# RedditSecretSanta2020_2.net
KiCad netlist of a schematic drawn in EAGLE
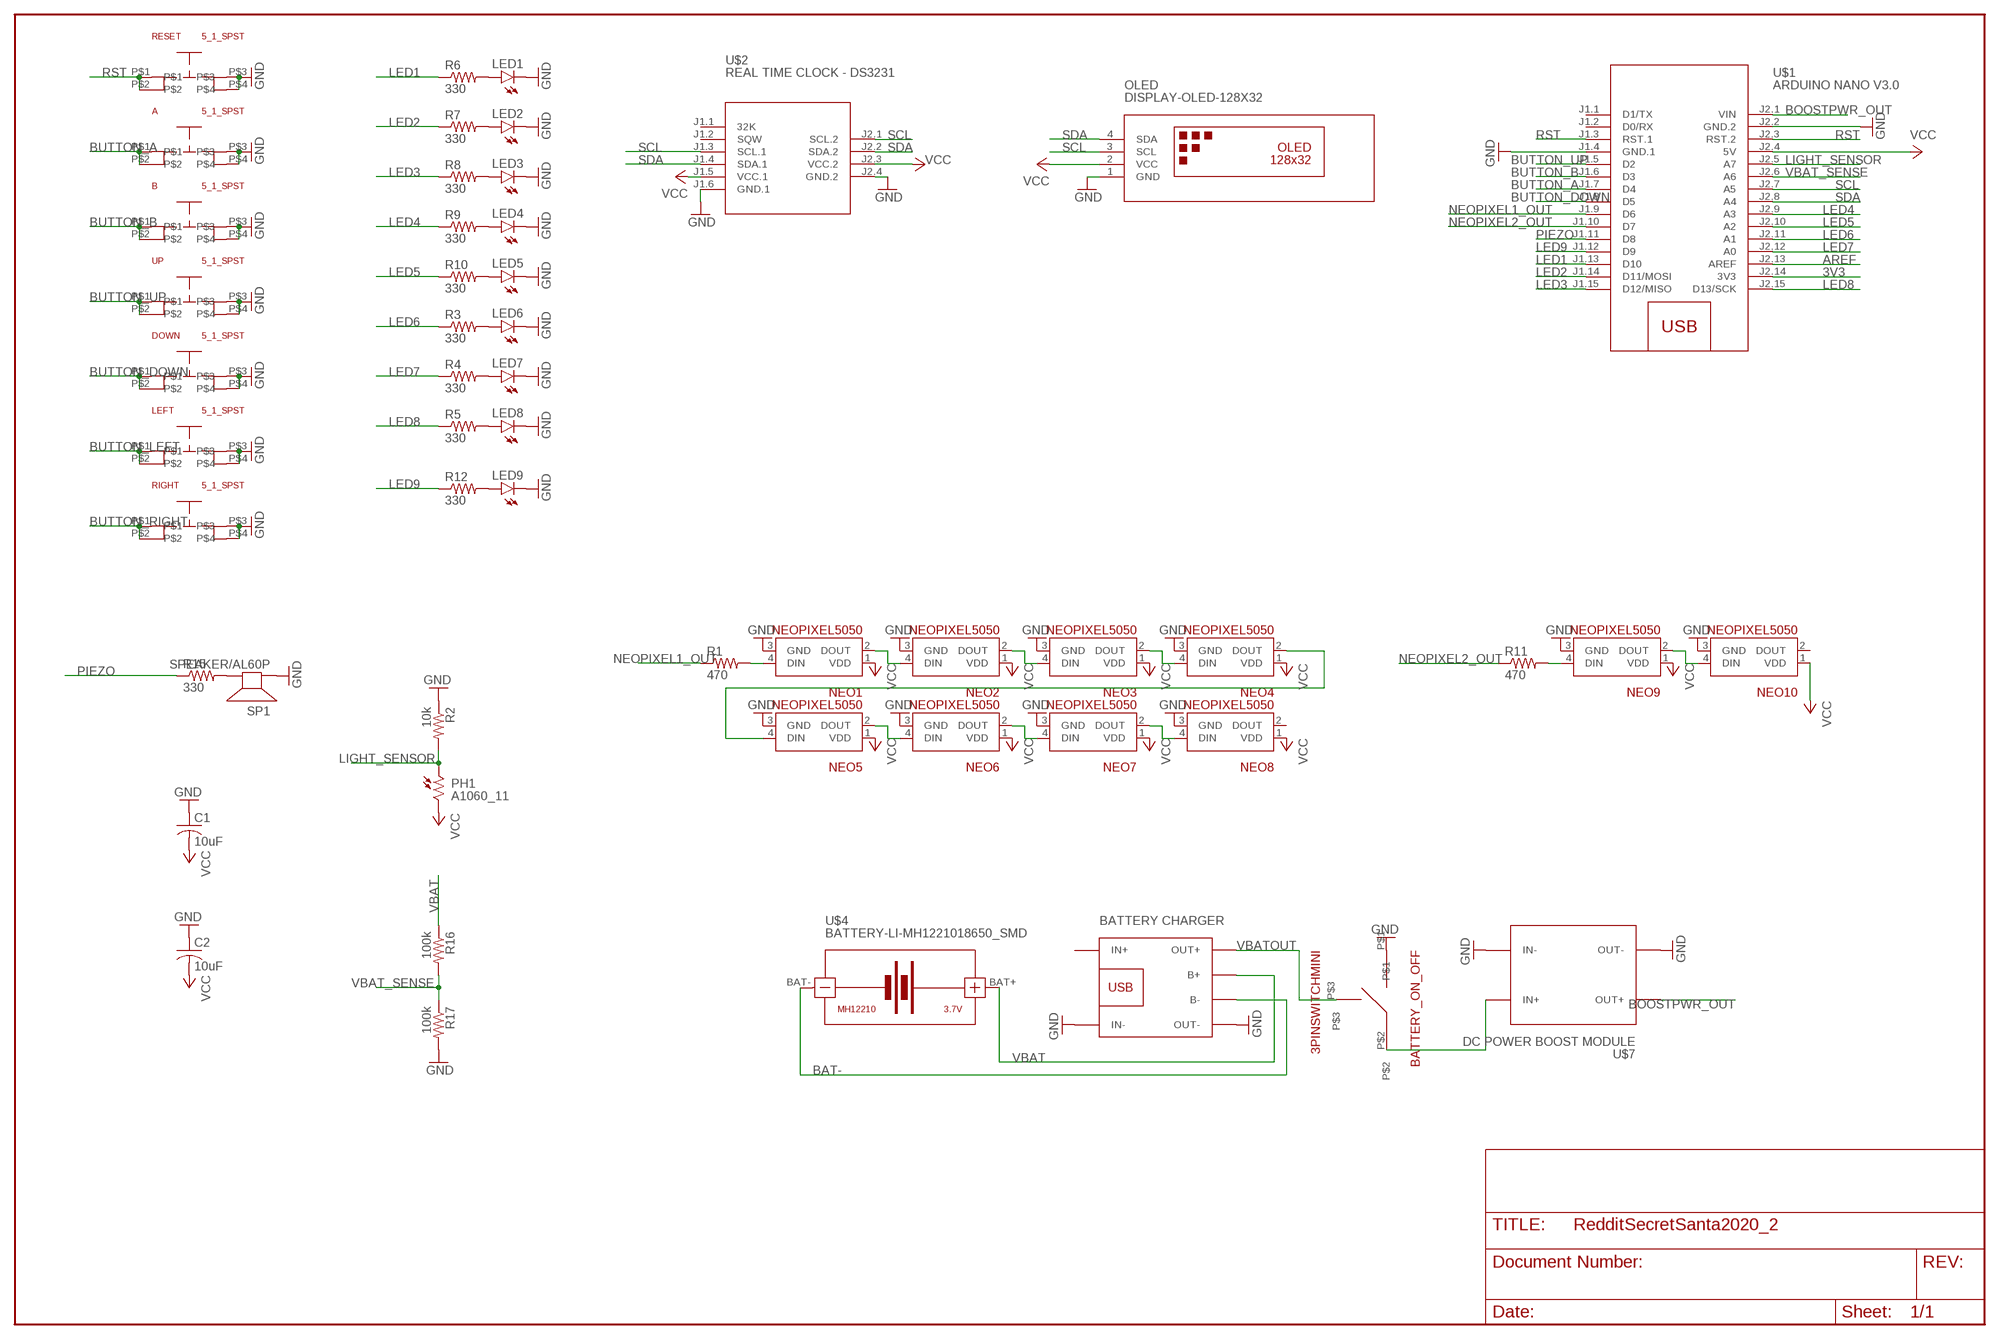
[diagram p0: schematic, sheet 1]

(export (version "E")
  (design (tool "Eeschema 10.0.6"))
  (components
    (comp (ref "A")
      (value "5_1_SPST")
      (footprint "eagle-import:5_1_SPST")
      (libsource (lib "eagle-import") (part "5_1_SPST"))
    )
    (comp (ref "B")
      (value "5_1_SPST")
      (footprint "eagle-import:5_1_SPST")
      (libsource (lib "eagle-import") (part "5_1_SPST"))
    )
    (comp (ref "BATTERY_ON_OFF")
      (value "3PINSWITCHMINI")
      (footprint "eagle-import:3PINMINI")
      (libsource (lib "eagle-import") (part "3PINSWITCHMINI"))
    )
    (comp (ref "C1")
      (value "10uF")
      (footprint "eagle-import:C0805")
      (libsource (lib "eagle-import") (part "C-USC0805"))
    )
    (comp (ref "C2")
      (value "10uF")
      (footprint "eagle-import:C0805")
      (libsource (lib "eagle-import") (part "C-USC0805"))
    )
    (comp (ref "DOWN")
      (value "5_1_SPST")
      (footprint "eagle-import:5_1_SPST")
      (libsource (lib "eagle-import") (part "5_1_SPST"))
    )
    (comp (ref "LED1")
      (value "LEDSML0805")
      (footprint "eagle-import:SML0805")
      (libsource (lib "eagle-import") (part "LEDSML0805"))
    )
    (comp (ref "LED2")
      (value "LEDSML0805")
      (footprint "eagle-import:SML0805")
      (libsource (lib "eagle-import") (part "LEDSML0805"))
    )
    (comp (ref "LED3")
      (value "LEDSML0805")
      (footprint "eagle-import:SML0805")
      (libsource (lib "eagle-import") (part "LEDSML0805"))
    )
    (comp (ref "LED4")
      (value "LEDSML0805")
      (footprint "eagle-import:SML0805")
      (libsource (lib "eagle-import") (part "LEDSML0805"))
    )
    (comp (ref "LED5")
      (value "LEDSML0805")
      (footprint "eagle-import:SML0805")
      (libsource (lib "eagle-import") (part "LEDSML0805"))
    )
    (comp (ref "LED6")
      (value "LEDSML0805")
      (footprint "eagle-import:SML0805")
      (libsource (lib "eagle-import") (part "LEDSML0805"))
    )
    (comp (ref "LED7")
      (value "LEDSML0805")
      (footprint "eagle-import:SML0805")
      (libsource (lib "eagle-import") (part "LEDSML0805"))
    )
    (comp (ref "LED8")
      (value "LEDSML0805")
      (footprint "eagle-import:SML0805")
      (libsource (lib "eagle-import") (part "LEDSML0805"))
    )
    (comp (ref "LED9")
      (value "LEDSML0805")
      (footprint "eagle-import:SML0805")
      (libsource (lib "eagle-import") (part "LEDSML0805"))
    )
    (comp (ref "LEFT")
      (value "5_1_SPST")
      (footprint "eagle-import:5_1_SPST")
      (libsource (lib "eagle-import") (part "5_1_SPST"))
    )
    (comp (ref "NEO1")
      (value "NEOPIXEL5050")
      (footprint "eagle-import:NEOPIXEL5050")
      (libsource (lib "eagle-import") (part "NEOPIXEL5050"))
    )
    (comp (ref "NEO2")
      (value "NEOPIXEL5050")
      (footprint "eagle-import:NEOPIXEL5050")
      (libsource (lib "eagle-import") (part "NEOPIXEL5050"))
    )
    (comp (ref "NEO3")
      (value "NEOPIXEL5050")
      (footprint "eagle-import:NEOPIXEL5050")
      (libsource (lib "eagle-import") (part "NEOPIXEL5050"))
    )
    (comp (ref "NEO4")
      (value "NEOPIXEL5050")
      (footprint "eagle-import:NEOPIXEL5050")
      (libsource (lib "eagle-import") (part "NEOPIXEL5050"))
    )
    (comp (ref "NEO5")
      (value "NEOPIXEL5050")
      (footprint "eagle-import:NEOPIXEL5050")
      (libsource (lib "eagle-import") (part "NEOPIXEL5050"))
    )
    (comp (ref "NEO6")
      (value "NEOPIXEL5050")
      (footprint "eagle-import:NEOPIXEL5050")
      (libsource (lib "eagle-import") (part "NEOPIXEL5050"))
    )
    (comp (ref "NEO7")
      (value "NEOPIXEL5050")
      (footprint "eagle-import:NEOPIXEL5050")
      (libsource (lib "eagle-import") (part "NEOPIXEL5050"))
    )
    (comp (ref "NEO8")
      (value "NEOPIXEL5050")
      (footprint "eagle-import:NEOPIXEL5050")
      (libsource (lib "eagle-import") (part "NEOPIXEL5050"))
    )
    (comp (ref "NEO9")
      (value "NEOPIXEL5050")
      (footprint "eagle-import:NEOPIXEL5050")
      (libsource (lib "eagle-import") (part "NEOPIXEL5050"))
    )
    (comp (ref "NEO10")
      (value "NEOPIXEL5050")
      (footprint "eagle-import:NEOPIXEL5050")
      (libsource (lib "eagle-import") (part "NEOPIXEL5050"))
    )
    (comp (ref "OLED")
      (value "DISPLAY-OLED-128X32")
      (footprint "eagle-import:DISPLAY-OLED-128X32")
      (libsource (lib "eagle-import") (part "DISPLAY-OLED-128X32"))
    )
    (comp (ref "PH1")
      (value "A1060_11")
      (footprint "eagle-import:T0-46-A10XX")
      (libsource (lib "eagle-import") (part "A1060_11"))
    )
    (comp (ref "R1")
      (value "470")
      (footprint "eagle-import:R0805")
      (libsource (lib "eagle-import") (part "R-US_R0805"))
    )
    (comp (ref "R2")
      (value "10k")
      (footprint "eagle-import:R0805")
      (libsource (lib "eagle-import") (part "R-US_R0805"))
    )
    (comp (ref "R3")
      (value "330")
      (footprint "eagle-import:R0805")
      (libsource (lib "eagle-import") (part "R-US_R0805"))
    )
    (comp (ref "R4")
      (value "330")
      (footprint "eagle-import:R0805")
      (libsource (lib "eagle-import") (part "R-US_R0805"))
    )
    (comp (ref "R5")
      (value "330")
      (footprint "eagle-import:R0805")
      (libsource (lib "eagle-import") (part "R-US_R0805"))
    )
    (comp (ref "R6")
      (value "330")
      (footprint "eagle-import:R0805")
      (libsource (lib "eagle-import") (part "R-US_R0805"))
    )
    (comp (ref "R7")
      (value "330")
      (footprint "eagle-import:R0805")
      (libsource (lib "eagle-import") (part "R-US_R0805"))
    )
    (comp (ref "R8")
      (value "330")
      (footprint "eagle-import:R0805")
      (libsource (lib "eagle-import") (part "R-US_R0805"))
    )
    (comp (ref "R9")
      (value "330")
      (footprint "eagle-import:R0805")
      (libsource (lib "eagle-import") (part "R-US_R0805"))
    )
    (comp (ref "R10")
      (value "330")
      (footprint "eagle-import:R0805")
      (libsource (lib "eagle-import") (part "R-US_R0805"))
    )
    (comp (ref "R11")
      (value "470")
      (footprint "eagle-import:R0805")
      (libsource (lib "eagle-import") (part "R-US_R0805"))
    )
    (comp (ref "R12")
      (value "330")
      (footprint "eagle-import:R0805")
      (libsource (lib "eagle-import") (part "R-US_R0805"))
    )
    (comp (ref "R15")
      (value "330")
      (footprint "eagle-import:R0805")
      (libsource (lib "eagle-import") (part "R-US_R0805"))
    )
    (comp (ref "R16")
      (value "100k")
      (footprint "eagle-import:R0805")
      (libsource (lib "eagle-import") (part "R-US_R0805"))
    )
    (comp (ref "R17")
      (value "100k")
      (footprint "eagle-import:R0805")
      (libsource (lib "eagle-import") (part "R-US_R0805"))
    )
    (comp (ref "RESET")
      (value "5_1_SPST")
      (footprint "eagle-import:5_1_SPST")
      (libsource (lib "eagle-import") (part "5_1_SPST"))
    )
    (comp (ref "RIGHT")
      (value "5_1_SPST")
      (footprint "eagle-import:5_1_SPST")
      (libsource (lib "eagle-import") (part "5_1_SPST"))
    )
    (comp (ref "SP1")
      (value "SPEAKER/AL60P")
      (footprint "eagle-import:AL60P")
      (libsource (lib "eagle-import") (part "SPEAKER/AL60P"))
    )
    (comp (ref "U$1")
      (value "ARDUINO NANO V3.0")
      (footprint "eagle-import:ARDUINO-NANO-3.0")
      (libsource (lib "eagle-import") (part "ARDUINO-NANO-3.0"))
    )
    (comp (ref "U$2")
      (value "REAL TIME CLOCK - DS3231")
      (footprint "eagle-import:RTC-DS3231-AT24C32")
      (libsource (lib "eagle-import") (part "RTC-DS3231-AT24C32"))
    )
    (comp (ref "U$4")
      (value "BATTERY-LI-MH1221018650_SMD")
      (footprint "eagle-import:BATTERY_18650_SMD")
      (libsource (lib "eagle-import") (part "BATTERY-LI-MH1221018650_SMD"))
    )
    (comp (ref "U$6")
      (value "BATTERY CHARGER")
      (footprint "eagle-import:BAT_CHARGE_LOW_FP")
      (libsource (lib "eagle-import") (part "BATTERY-CHARGER-LI-PROTLOW_FP"))
    )
    (comp (ref "U$7")
      (value "DC POWER BOOST MODULE")
      (footprint "eagle-import:DC-DC-STEP-UP-LOW_FP")
      (libsource (lib "eagle-import") (part "DC-DC-STEP-UP-MT3608LOW_FP"))
    )
    (comp (ref "UP")
      (value "5_1_SPST")
      (footprint "eagle-import:5_1_SPST")
      (libsource (lib "eagle-import") (part "5_1_SPST"))
    )
  )
  (nets
    (net (code "1") (name "/3V3") (class "Default")
      (node (ref "U$1") (pin "J2.14") (pinfunction "3V3_J2.14") (pintype "power_in"))
    )
    (net (code "2") (name "/AREF") (class "Default")
      (node (ref "U$1") (pin "J2.13") (pinfunction "AREF_J2.13") (pintype "bidirectional"))
    )
    (net (code "3") (name "/BAT-") (class "Default")
      (node (ref "U$4") (pin "BAT-") (pinfunction "BAT-_BAT-") (pintype "power_in"))
      (node (ref "U$6") (pin "B-") (pinfunction "B-_B-") (pintype "bidirectional"))
    )
    (net (code "4") (name "/BOOSTPWR_OUT") (class "Default")
      (node (ref "U$1") (pin "J2.1") (pinfunction "VIN_J2.1") (pintype "power_in"))
      (node (ref "U$7") (pin "OUT+") (pinfunction "OUT+_OUT+") (pintype "bidirectional"))
    )
    (net (code "5") (name "/BUTTON_A") (class "Default")
      (node (ref "A") (pin "P$1") (pinfunction "P$1_P$1") (pintype "bidirectional"))
      (node (ref "A") (pin "P$2") (pinfunction "P$2_P$2") (pintype "bidirectional"))
      (node (ref "U$1") (pin "J1.7") (pinfunction "D4_J1.7") (pintype "bidirectional"))
    )
    (net (code "6") (name "/BUTTON_B") (class "Default")
      (node (ref "B") (pin "P$1") (pinfunction "P$1_P$1") (pintype "bidirectional"))
      (node (ref "B") (pin "P$2") (pinfunction "P$2_P$2") (pintype "bidirectional"))
      (node (ref "U$1") (pin "J1.6") (pinfunction "D3_J1.6") (pintype "bidirectional"))
    )
    (net (code "7") (name "/BUTTON_DOWN") (class "Default")
      (node (ref "DOWN") (pin "P$1") (pinfunction "P$1_P$1") (pintype "bidirectional"))
      (node (ref "DOWN") (pin "P$2") (pinfunction "P$2_P$2") (pintype "bidirectional"))
      (node (ref "U$1") (pin "J1.8") (pinfunction "D5_J1.8") (pintype "bidirectional"))
    )
    (net (code "8") (name "/BUTTON_LEFT") (class "Default")
      (node (ref "LEFT") (pin "P$1") (pinfunction "P$1_P$1") (pintype "bidirectional"))
      (node (ref "LEFT") (pin "P$2") (pinfunction "P$2_P$2") (pintype "bidirectional"))
    )
    (net (code "9") (name "/BUTTON_RIGHT") (class "Default")
      (node (ref "RIGHT") (pin "P$1") (pinfunction "P$1_P$1") (pintype "bidirectional"))
      (node (ref "RIGHT") (pin "P$2") (pinfunction "P$2_P$2") (pintype "bidirectional"))
    )
    (net (code "10") (name "/BUTTON_UP") (class "Default")
      (node (ref "U$1") (pin "J1.5") (pinfunction "D2_J1.5") (pintype "bidirectional"))
      (node (ref "UP") (pin "P$1") (pinfunction "P$1_P$1") (pintype "bidirectional"))
      (node (ref "UP") (pin "P$2") (pinfunction "P$2_P$2") (pintype "bidirectional"))
    )
    (net (code "11") (name "/LED1") (class "Default")
      (node (ref "R6") (pin "1") (pinfunction "1_1") (pintype "passive"))
      (node (ref "U$1") (pin "J1.13") (pinfunction "D10_J1.13") (pintype "bidirectional"))
    )
    (net (code "12") (name "/LED2") (class "Default")
      (node (ref "R7") (pin "1") (pinfunction "1_1") (pintype "passive"))
      (node (ref "U$1") (pin "J1.14") (pinfunction "D11/MOSI_J1.14") (pintype "bidirectional"))
    )
    (net (code "13") (name "/LED3") (class "Default")
      (node (ref "R8") (pin "1") (pinfunction "1_1") (pintype "passive"))
      (node (ref "U$1") (pin "J1.15") (pinfunction "D12/MISO_J1.15") (pintype "bidirectional"))
    )
    (net (code "14") (name "/LED4") (class "Default")
      (node (ref "R9") (pin "1") (pinfunction "1_1") (pintype "passive"))
      (node (ref "U$1") (pin "J2.9") (pinfunction "A3_J2.9") (pintype "bidirectional"))
    )
    (net (code "15") (name "/LED5") (class "Default")
      (node (ref "R10") (pin "1") (pinfunction "1_1") (pintype "passive"))
      (node (ref "U$1") (pin "J2.10") (pinfunction "A2_J2.10") (pintype "bidirectional"))
    )
    (net (code "16") (name "/LED6") (class "Default")
      (node (ref "R3") (pin "1") (pinfunction "1_1") (pintype "passive"))
      (node (ref "U$1") (pin "J2.11") (pinfunction "A1_J2.11") (pintype "bidirectional"))
    )
    (net (code "17") (name "/LED7") (class "Default")
      (node (ref "R4") (pin "1") (pinfunction "1_1") (pintype "passive"))
      (node (ref "U$1") (pin "J2.12") (pinfunction "A0_J2.12") (pintype "bidirectional"))
    )
    (net (code "18") (name "/LED8") (class "Default")
      (node (ref "R5") (pin "1") (pinfunction "1_1") (pintype "passive"))
      (node (ref "U$1") (pin "J2.15") (pinfunction "D13/SCK_J2.15") (pintype "bidirectional"))
    )
    (net (code "19") (name "/LED9") (class "Default")
      (node (ref "R12") (pin "1") (pinfunction "1_1") (pintype "passive"))
      (node (ref "U$1") (pin "J1.12") (pinfunction "D9_J1.12") (pintype "bidirectional"))
    )
    (net (code "20") (name "/LIGHT_SENSOR") (class "Default")
      (node (ref "PH1") (pin "1") (pinfunction "1_1") (pintype "passive"))
      (node (ref "R2") (pin "2") (pinfunction "2_2") (pintype "passive"))
      (node (ref "U$1") (pin "J2.5") (pinfunction "A7_J2.5") (pintype "bidirectional"))
    )
    (net (code "21") (name "/NEOPIXEL1_OUT") (class "Default")
      (node (ref "R1") (pin "1") (pinfunction "1_1") (pintype "passive"))
      (node (ref "U$1") (pin "J1.9") (pinfunction "D6_J1.9") (pintype "bidirectional"))
    )
    (net (code "22") (name "/NEOPIXEL2_OUT") (class "Default")
      (node (ref "R11") (pin "1") (pinfunction "1_1") (pintype "passive"))
      (node (ref "U$1") (pin "J1.10") (pinfunction "D7_J1.10") (pintype "bidirectional"))
    )
    (net (code "23") (name "/PIEZO") (class "Default")
      (node (ref "R15") (pin "1") (pinfunction "1_1") (pintype "passive"))
      (node (ref "U$1") (pin "J1.11") (pinfunction "D8_J1.11") (pintype "bidirectional"))
    )
    (net (code "24") (name "/RST") (class "Default")
      (node (ref "RESET") (pin "P$1") (pinfunction "P$1_P$1") (pintype "bidirectional"))
      (node (ref "RESET") (pin "P$2") (pinfunction "P$2_P$2") (pintype "bidirectional"))
      (node (ref "U$1") (pin "J1.3") (pinfunction "RST.1_J1.3") (pintype "bidirectional"))
      (node (ref "U$1") (pin "J2.3") (pinfunction "RST.2_J2.3") (pintype "bidirectional"))
    )
    (net (code "25") (name "/SCL") (class "Default")
      (node (ref "OLED") (pin "3") (pinfunction "SCL_3") (pintype "bidirectional"))
      (node (ref "U$1") (pin "J2.7") (pinfunction "A5_J2.7") (pintype "bidirectional"))
      (node (ref "U$2") (pin "J1.3") (pinfunction "SCL.1_J1.3") (pintype "bidirectional"))
      (node (ref "U$2") (pin "J2.1") (pinfunction "SCL.2_J2.1") (pintype "bidirectional"))
    )
    (net (code "26") (name "/SDA") (class "Default")
      (node (ref "OLED") (pin "4") (pinfunction "SDA_4") (pintype "bidirectional"))
      (node (ref "U$1") (pin "J2.8") (pinfunction "A4_J2.8") (pintype "bidirectional"))
      (node (ref "U$2") (pin "J1.4") (pinfunction "SDA.1_J1.4") (pintype "bidirectional"))
      (node (ref "U$2") (pin "J2.2") (pinfunction "SDA.2_J2.2") (pintype "bidirectional"))
    )
    (net (code "27") (name "/VBAT") (class "Default")
      (node (ref "R16") (pin "1") (pinfunction "1_1") (pintype "passive"))
      (node (ref "U$4") (pin "BAT+") (pinfunction "BAT+_BAT+") (pintype "power_in"))
      (node (ref "U$6") (pin "B+") (pinfunction "B+_B+") (pintype "bidirectional"))
    )
    (net (code "28") (name "/VBATOUT") (class "Default")
      (node (ref "BATTERY_ON_OFF") (pin "P$3") (pinfunction "P$3_P$3") (pintype "bidirectional"))
      (node (ref "U$6") (pin "OUT+") (pinfunction "OUT+_OUT+") (pintype "bidirectional"))
    )
    (net (code "29") (name "/VBAT_SENSE") (class "Default")
      (node (ref "R16") (pin "2") (pinfunction "2_2") (pintype "passive"))
      (node (ref "R17") (pin "1") (pinfunction "1_1") (pintype "passive"))
      (node (ref "U$1") (pin "J2.6") (pinfunction "A6_J2.6") (pintype "bidirectional"))
    )
    (net (code "30") (name "GND") (class "Default")
      (node (ref "A") (pin "P$3") (pinfunction "P$3_P$3") (pintype "bidirectional"))
      (node (ref "A") (pin "P$4") (pinfunction "P$4_P$4") (pintype "bidirectional"))
      (node (ref "B") (pin "P$3") (pinfunction "P$3_P$3") (pintype "bidirectional"))
      (node (ref "B") (pin "P$4") (pinfunction "P$4_P$4") (pintype "bidirectional"))
      (node (ref "BATTERY_ON_OFF") (pin "P$1") (pinfunction "P$1_P$1") (pintype "bidirectional"))
      (node (ref "C1") (pin "1") (pinfunction "1_1") (pintype "passive"))
      (node (ref "C2") (pin "1") (pinfunction "1_1") (pintype "passive"))
      (node (ref "DOWN") (pin "P$3") (pinfunction "P$3_P$3") (pintype "bidirectional"))
      (node (ref "DOWN") (pin "P$4") (pinfunction "P$4_P$4") (pintype "bidirectional"))
      (node (ref "LED1") (pin "C") (pinfunction "C_C") (pintype "passive"))
      (node (ref "LED2") (pin "C") (pinfunction "C_C") (pintype "passive"))
      (node (ref "LED3") (pin "C") (pinfunction "C_C") (pintype "passive"))
      (node (ref "LED4") (pin "C") (pinfunction "C_C") (pintype "passive"))
      (node (ref "LED5") (pin "C") (pinfunction "C_C") (pintype "passive"))
      (node (ref "LED6") (pin "C") (pinfunction "C_C") (pintype "passive"))
      (node (ref "LED7") (pin "C") (pinfunction "C_C") (pintype "passive"))
      (node (ref "LED8") (pin "C") (pinfunction "C_C") (pintype "passive"))
      (node (ref "LED9") (pin "C") (pinfunction "C_C") (pintype "passive"))
      (node (ref "LEFT") (pin "P$3") (pinfunction "P$3_P$3") (pintype "bidirectional"))
      (node (ref "LEFT") (pin "P$4") (pinfunction "P$4_P$4") (pintype "bidirectional"))
      (node (ref "NEO1") (pin "3") (pinfunction "GND_3") (pintype "bidirectional"))
      (node (ref "NEO10") (pin "3") (pinfunction "GND_3") (pintype "bidirectional"))
      (node (ref "NEO2") (pin "3") (pinfunction "GND_3") (pintype "bidirectional"))
      (node (ref "NEO3") (pin "3") (pinfunction "GND_3") (pintype "bidirectional"))
      (node (ref "NEO4") (pin "3") (pinfunction "GND_3") (pintype "bidirectional"))
      (node (ref "NEO5") (pin "3") (pinfunction "GND_3") (pintype "bidirectional"))
      (node (ref "NEO6") (pin "3") (pinfunction "GND_3") (pintype "bidirectional"))
      (node (ref "NEO7") (pin "3") (pinfunction "GND_3") (pintype "bidirectional"))
      (node (ref "NEO8") (pin "3") (pinfunction "GND_3") (pintype "bidirectional"))
      (node (ref "NEO9") (pin "3") (pinfunction "GND_3") (pintype "bidirectional"))
      (node (ref "OLED") (pin "1") (pinfunction "GND_1") (pintype "power_in"))
      (node (ref "R17") (pin "2") (pinfunction "2_2") (pintype "passive"))
      (node (ref "R2") (pin "1") (pinfunction "1_1") (pintype "passive"))
      (node (ref "RESET") (pin "P$3") (pinfunction "P$3_P$3") (pintype "bidirectional"))
      (node (ref "RESET") (pin "P$4") (pinfunction "P$4_P$4") (pintype "bidirectional"))
      (node (ref "RIGHT") (pin "P$3") (pinfunction "P$3_P$3") (pintype "bidirectional"))
      (node (ref "RIGHT") (pin "P$4") (pinfunction "P$4_P$4") (pintype "bidirectional"))
      (node (ref "SP1") (pin "1") (pinfunction "+_1") (pintype "passive"))
      (node (ref "U$1") (pin "J1.4") (pinfunction "GND.1_J1.4") (pintype "power_in"))
      (node (ref "U$1") (pin "J2.2") (pinfunction "GND.2_J2.2") (pintype "power_in"))
      (node (ref "U$2") (pin "J1.6") (pinfunction "GND.1_J1.6") (pintype "power_in"))
      (node (ref "U$2") (pin "J2.4") (pinfunction "GND.2_J2.4") (pintype "power_in"))
      (node (ref "U$6") (pin "IN-") (pinfunction "IN-_IN-") (pintype "bidirectional"))
      (node (ref "U$6") (pin "OUT-") (pinfunction "OUT-_OUT-") (pintype "bidirectional"))
      (node (ref "U$7") (pin "IN-") (pinfunction "IN-_IN-") (pintype "bidirectional"))
      (node (ref "U$7") (pin "OUT-") (pinfunction "OUT-_OUT-") (pintype "bidirectional"))
      (node (ref "UP") (pin "P$3") (pinfunction "P$3_P$3") (pintype "bidirectional"))
      (node (ref "UP") (pin "P$4") (pinfunction "P$4_P$4") (pintype "bidirectional"))
    )
    (net (code "31") (name "Net-(BATTERY_ON_OFF-PadP$2)") (class "Default")
      (node (ref "BATTERY_ON_OFF") (pin "P$2") (pinfunction "P$2_P$2") (pintype "bidirectional"))
      (node (ref "U$7") (pin "IN+") (pinfunction "IN+_IN+") (pintype "bidirectional"))
    )
    (net (code "32") (name "Net-(LED1-PadA)") (class "Default")
      (node (ref "LED1") (pin "A") (pinfunction "A_A") (pintype "passive"))
      (node (ref "R6") (pin "2") (pinfunction "2_2") (pintype "passive"))
    )
    (net (code "33") (name "Net-(LED2-PadA)") (class "Default")
      (node (ref "LED2") (pin "A") (pinfunction "A_A") (pintype "passive"))
      (node (ref "R7") (pin "2") (pinfunction "2_2") (pintype "passive"))
    )
    (net (code "34") (name "Net-(LED3-PadA)") (class "Default")
      (node (ref "LED3") (pin "A") (pinfunction "A_A") (pintype "passive"))
      (node (ref "R8") (pin "2") (pinfunction "2_2") (pintype "passive"))
    )
    (net (code "35") (name "Net-(LED4-PadA)") (class "Default")
      (node (ref "LED4") (pin "A") (pinfunction "A_A") (pintype "passive"))
      (node (ref "R9") (pin "2") (pinfunction "2_2") (pintype "passive"))
    )
    (net (code "36") (name "Net-(LED5-PadA)") (class "Default")
      (node (ref "LED5") (pin "A") (pinfunction "A_A") (pintype "passive"))
      (node (ref "R10") (pin "2") (pinfunction "2_2") (pintype "passive"))
    )
    (net (code "37") (name "Net-(LED6-PadA)") (class "Default")
      (node (ref "LED6") (pin "A") (pinfunction "A_A") (pintype "passive"))
      (node (ref "R3") (pin "2") (pinfunction "2_2") (pintype "passive"))
    )
    (net (code "38") (name "Net-(LED7-PadA)") (class "Default")
      (node (ref "LED7") (pin "A") (pinfunction "A_A") (pintype "passive"))
      (node (ref "R4") (pin "2") (pinfunction "2_2") (pintype "passive"))
    )
    (net (code "39") (name "Net-(LED8-PadA)") (class "Default")
      (node (ref "LED8") (pin "A") (pinfunction "A_A") (pintype "passive"))
      (node (ref "R5") (pin "2") (pinfunction "2_2") (pintype "passive"))
    )
    (net (code "40") (name "Net-(LED9-PadA)") (class "Default")
      (node (ref "LED9") (pin "A") (pinfunction "A_A") (pintype "passive"))
      (node (ref "R12") (pin "2") (pinfunction "2_2") (pintype "passive"))
    )
    (net (code "41") (name "Net-(NEO1-DIN)") (class "Default")
      (node (ref "NEO1") (pin "4") (pinfunction "DIN_4") (pintype "bidirectional"))
      (node (ref "R1") (pin "2") (pinfunction "2_2") (pintype "passive"))
    )
    (net (code "42") (name "Net-(NEO1-DOUT)") (class "Default")
      (node (ref "NEO1") (pin "2") (pinfunction "DOUT_2") (pintype "bidirectional"))
      (node (ref "NEO2") (pin "4") (pinfunction "DIN_4") (pintype "bidirectional"))
    )
    (net (code "43") (name "Net-(NEO2-DOUT)") (class "Default")
      (node (ref "NEO2") (pin "2") (pinfunction "DOUT_2") (pintype "bidirectional"))
      (node (ref "NEO3") (pin "4") (pinfunction "DIN_4") (pintype "bidirectional"))
    )
    (net (code "44") (name "Net-(NEO3-DOUT)") (class "Default")
      (node (ref "NEO3") (pin "2") (pinfunction "DOUT_2") (pintype "bidirectional"))
      (node (ref "NEO4") (pin "4") (pinfunction "DIN_4") (pintype "bidirectional"))
    )
    (net (code "45") (name "Net-(NEO4-DOUT)") (class "Default")
      (node (ref "NEO4") (pin "2") (pinfunction "DOUT_2") (pintype "bidirectional"))
      (node (ref "NEO5") (pin "4") (pinfunction "DIN_4") (pintype "bidirectional"))
    )
    (net (code "46") (name "Net-(NEO5-DOUT)") (class "Default")
      (node (ref "NEO5") (pin "2") (pinfunction "DOUT_2") (pintype "bidirectional"))
      (node (ref "NEO6") (pin "4") (pinfunction "DIN_4") (pintype "bidirectional"))
    )
    (net (code "47") (name "Net-(NEO6-DOUT)") (class "Default")
      (node (ref "NEO6") (pin "2") (pinfunction "DOUT_2") (pintype "bidirectional"))
      (node (ref "NEO7") (pin "4") (pinfunction "DIN_4") (pintype "bidirectional"))
    )
    (net (code "48") (name "Net-(NEO7-DOUT)") (class "Default")
      (node (ref "NEO7") (pin "2") (pinfunction "DOUT_2") (pintype "bidirectional"))
      (node (ref "NEO8") (pin "4") (pinfunction "DIN_4") (pintype "bidirectional"))
    )
    (net (code "49") (name "Net-(NEO9-DIN)") (class "Default")
      (node (ref "NEO9") (pin "4") (pinfunction "DIN_4") (pintype "bidirectional"))
      (node (ref "R11") (pin "2") (pinfunction "2_2") (pintype "passive"))
    )
    (net (code "50") (name "Net-(NEO10-DIN)") (class "Default")
      (node (ref "NEO10") (pin "4") (pinfunction "DIN_4") (pintype "bidirectional"))
      (node (ref "NEO9") (pin "2") (pinfunction "DOUT_2") (pintype "bidirectional"))
    )
    (net (code "51") (name "Net-(SP1--)") (class "Default")
      (node (ref "R15") (pin "2") (pinfunction "2_2") (pintype "passive"))
      (node (ref "SP1") (pin "2") (pinfunction "-_2") (pintype "passive"))
    )
    (net (code "52") (name "VCC") (class "Default")
      (node (ref "C1") (pin "2") (pinfunction "2_2") (pintype "passive"))
      (node (ref "C2") (pin "2") (pinfunction "2_2") (pintype "passive"))
      (node (ref "NEO1") (pin "1") (pinfunction "VDD_1") (pintype "bidirectional"))
      (node (ref "NEO10") (pin "1") (pinfunction "VDD_1") (pintype "bidirectional"))
      (node (ref "NEO2") (pin "1") (pinfunction "VDD_1") (pintype "bidirectional"))
      (node (ref "NEO3") (pin "1") (pinfunction "VDD_1") (pintype "bidirectional"))
      (node (ref "NEO4") (pin "1") (pinfunction "VDD_1") (pintype "bidirectional"))
      (node (ref "NEO5") (pin "1") (pinfunction "VDD_1") (pintype "bidirectional"))
      (node (ref "NEO6") (pin "1") (pinfunction "VDD_1") (pintype "bidirectional"))
      (node (ref "NEO7") (pin "1") (pinfunction "VDD_1") (pintype "bidirectional"))
      (node (ref "NEO8") (pin "1") (pinfunction "VDD_1") (pintype "bidirectional"))
      (node (ref "NEO9") (pin "1") (pinfunction "VDD_1") (pintype "bidirectional"))
      (node (ref "OLED") (pin "2") (pinfunction "VCC_2") (pintype "power_in"))
      (node (ref "PH1") (pin "2") (pinfunction "2_2") (pintype "passive"))
      (node (ref "U$1") (pin "J2.4") (pinfunction "5V_J2.4") (pintype "power_in"))
      (node (ref "U$2") (pin "J1.5") (pinfunction "VCC.1_J1.5") (pintype "power_in"))
      (node (ref "U$2") (pin "J2.3") (pinfunction "VCC.2_J2.3") (pintype "power_in"))
    )
    (net (code "53") (name "unconnected-(NEO8-DOUT-Pad2)") (class "Default")
      (node (ref "NEO8") (pin "2") (pinfunction "DOUT_2") (pintype "bidirectional"))
    )
    (net (code "54") (name "unconnected-(NEO10-DOUT-Pad2)") (class "Default")
      (node (ref "NEO10") (pin "2") (pinfunction "DOUT_2") (pintype "bidirectional"))
    )
    (net (code "55") (name "unconnected-(U$1-D0{slash}RX-PadJ1.2)") (class "Default")
      (node (ref "U$1") (pin "J1.2") (pinfunction "D0/RX_J1.2") (pintype "bidirectional"))
    )
    (net (code "56") (name "unconnected-(U$1-D1{slash}TX-PadJ1.1)") (class "Default")
      (node (ref "U$1") (pin "J1.1") (pinfunction "D1/TX_J1.1") (pintype "bidirectional"))
    )
    (net (code "57") (name "unconnected-(U$2-32K-PadJ1.1)") (class "Default")
      (node (ref "U$2") (pin "J1.1") (pinfunction "32K_J1.1") (pintype "bidirectional"))
    )
    (net (code "58") (name "unconnected-(U$2-SQW-PadJ1.2)") (class "Default")
      (node (ref "U$2") (pin "J1.2") (pinfunction "SQW_J1.2") (pintype "bidirectional"))
    )
    (net (code "59") (name "unconnected-(U$6-PadIN+)") (class "Default")
      (node (ref "U$6") (pin "IN+") (pinfunction "IN+_IN+") (pintype "bidirectional"))
    )
  )
)
